# rapidshark-clip-detector-mk-1_2.net
KiCad netlist of a schematic drawn in EAGLE
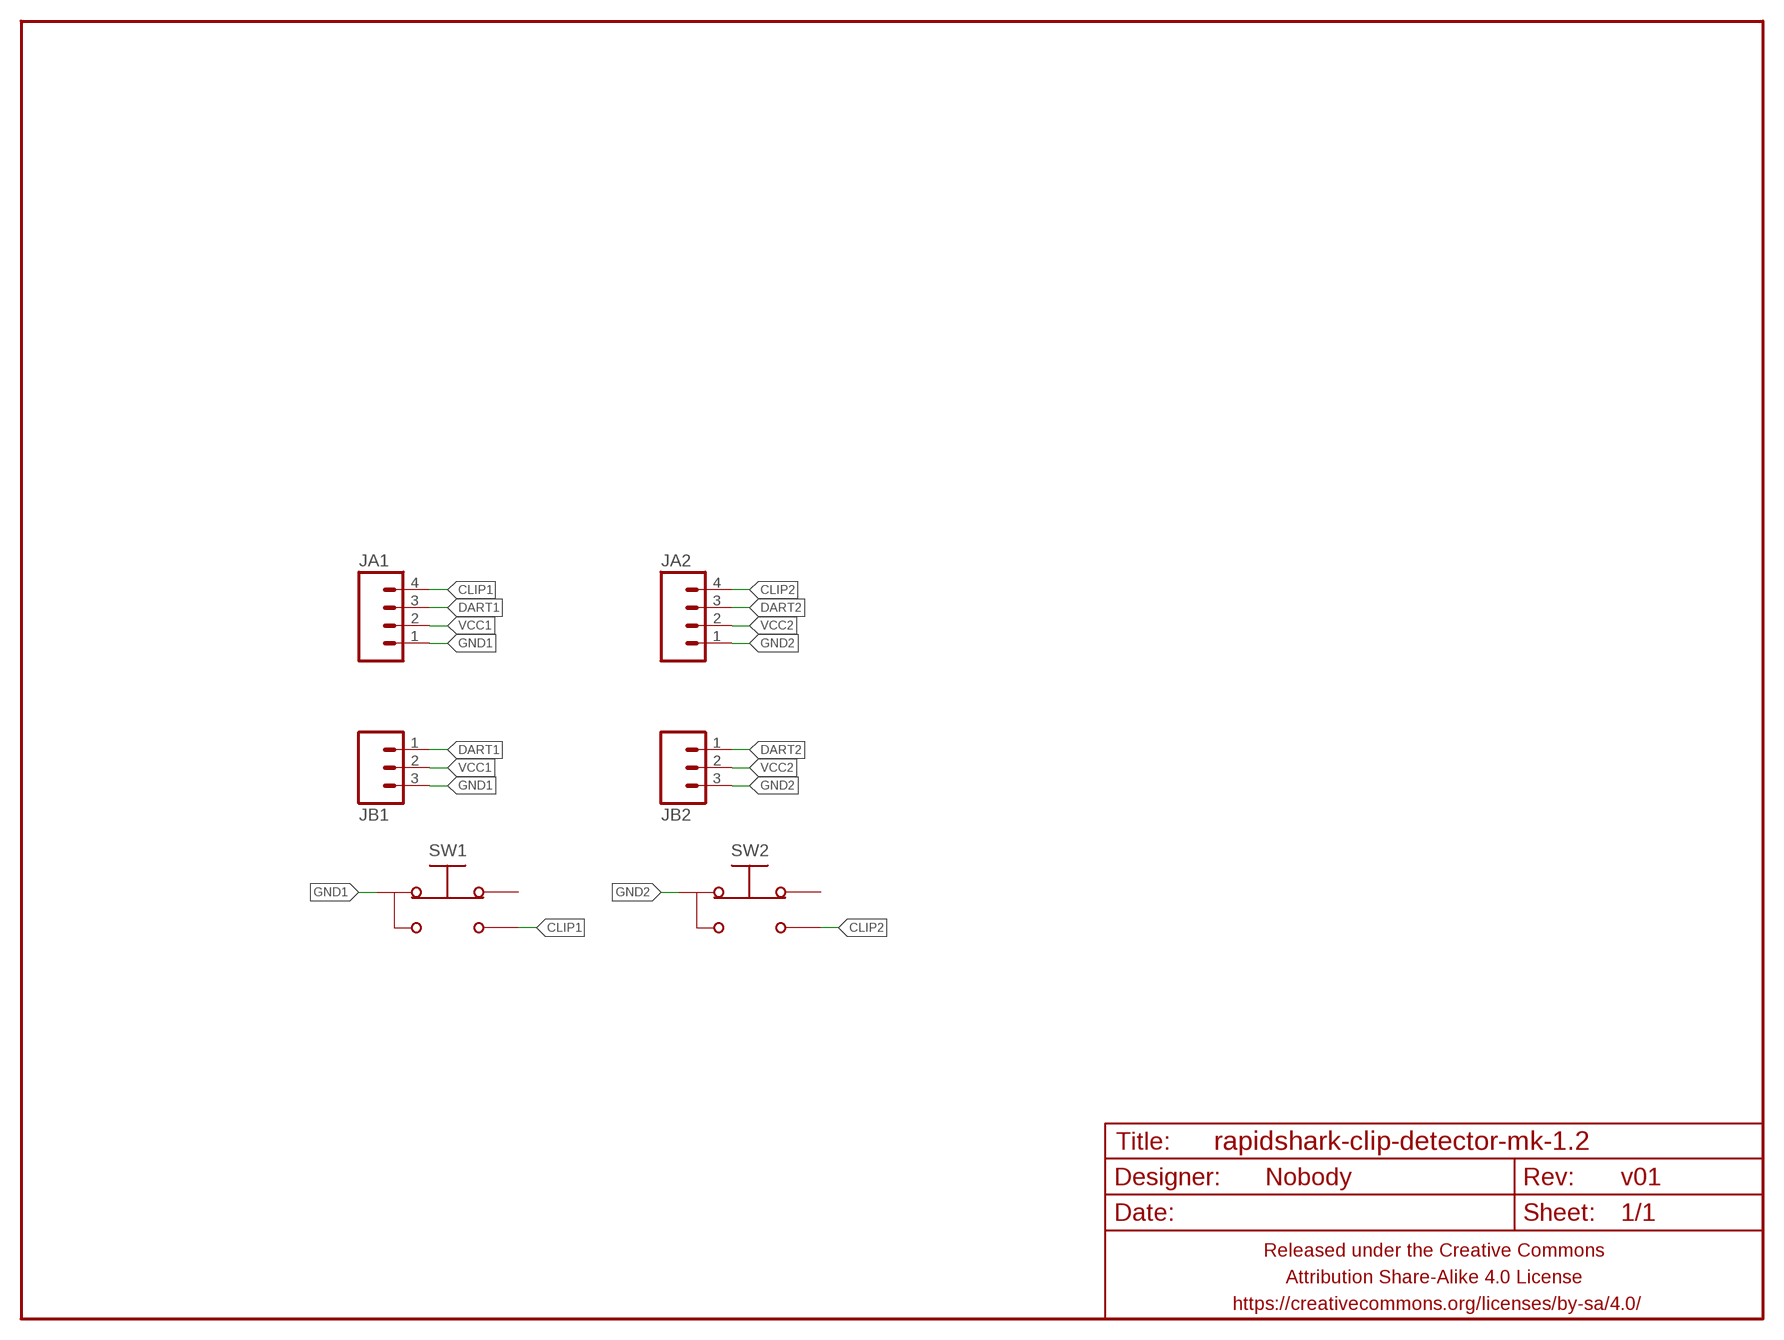
[diagram p0: schematic, sheet 1]

(export (version "E")
  (design (tool "Eeschema 10.0.6"))
  (components
    (comp (ref "FRAME1")
      (value "FRAME-LETTERNO_PACKAGE")
      (footprint "eagle-import:DUMMY")
      (fields (field (name "DESIGNER") "Nobody"))
      (libsource (lib "eagle-import") (part "FRAME-LETTERNO_PACKAGE"))
    )
    (comp (ref "JA1")
      (value "M04JST-PTH-VERT")
      (footprint "eagle-import:JST-4-PH-VERT-PTH")
      (libsource (lib "eagle-import") (part "M04JST-PTH-VERT"))
    )
    (comp (ref "JA2")
      (value "M04JST-PTH-VERT")
      (footprint "eagle-import:JST-4-PH-VERT-PTH")
      (libsource (lib "eagle-import") (part "M04JST-PTH-VERT"))
    )
    (comp (ref "JB1")
      (value "M03JST-PTH-VERT")
      (footprint "eagle-import:JST-3-PH-VERT-PTH")
      (libsource (lib "eagle-import") (part "M03JST-PTH-VERT"))
    )
    (comp (ref "JB2")
      (value "M03JST-PTH-VERT")
      (footprint "eagle-import:JST-3-PH-VERT-PTH")
      (libsource (lib "eagle-import") (part "M03JST-PTH-VERT"))
    )
    (comp (ref "SW1")
      (value "SPDT-NO-TACTPTH-RA-DETECT-3MM")
      (footprint "eagle-import:SWITCH-DETECH-SPDT-3MM")
      (libsource (lib "eagle-import") (part "SPDT-NO-TACTPTH-RA-DETECT-3MM"))
    )
    (comp (ref "SW2")
      (value "SPDT-NO-TACTPTH-RA-DETECT-3MM")
      (footprint "eagle-import:SWITCH-DETECH-SPDT-3MM")
      (libsource (lib "eagle-import") (part "SPDT-NO-TACTPTH-RA-DETECT-3MM"))
    )
  )
  (nets
    (net (code "1") (name "CLIP1") (class "Default")
      (node (ref "JA1") (pin "4") (pinfunction "4_4") (pintype "passive"))
      (node (ref "SW1") (pin "3") (pinfunction "NO_3") (pintype "bidirectional"))
    )
    (net (code "2") (name "CLIP2") (class "Default")
      (node (ref "JA2") (pin "4") (pinfunction "4_4") (pintype "passive"))
      (node (ref "SW2") (pin "3") (pinfunction "NO_3") (pintype "bidirectional"))
    )
    (net (code "3") (name "DART1") (class "Default")
      (node (ref "JA1") (pin "3") (pinfunction "3_3") (pintype "passive"))
      (node (ref "JB1") (pin "1") (pinfunction "1_1") (pintype "passive"))
    )
    (net (code "4") (name "DART2") (class "Default")
      (node (ref "JA2") (pin "3") (pinfunction "3_3") (pintype "passive"))
      (node (ref "JB2") (pin "1") (pinfunction "1_1") (pintype "passive"))
    )
    (net (code "5") (name "GND1") (class "Default")
      (node (ref "JA1") (pin "1") (pinfunction "1_1") (pintype "passive"))
      (node (ref "JB1") (pin "3") (pinfunction "3_3") (pintype "passive"))
      (node (ref "SW1") (pin "2") (pinfunction "COM_2") (pintype "bidirectional"))
    )
    (net (code "6") (name "GND2") (class "Default")
      (node (ref "JA2") (pin "1") (pinfunction "1_1") (pintype "passive"))
      (node (ref "JB2") (pin "3") (pinfunction "3_3") (pintype "passive"))
      (node (ref "SW2") (pin "2") (pinfunction "COM_2") (pintype "bidirectional"))
    )
    (net (code "7") (name "VCC1") (class "Default")
      (node (ref "JA1") (pin "2") (pinfunction "2_2") (pintype "passive"))
      (node (ref "JB1") (pin "2") (pinfunction "2_2") (pintype "passive"))
    )
    (net (code "8") (name "VCC2") (class "Default")
      (node (ref "JA2") (pin "2") (pinfunction "2_2") (pintype "passive"))
      (node (ref "JB2") (pin "2") (pinfunction "2_2") (pintype "passive"))
    )
    (net (code "9") (name "unconnected-(SW1-NC-Pad1)") (class "Default")
      (node (ref "SW1") (pin "1") (pinfunction "NC_1") (pintype "bidirectional"))
    )
    (net (code "10") (name "unconnected-(SW2-NC-Pad1)") (class "Default")
      (node (ref "SW2") (pin "1") (pinfunction "NC_1") (pintype "bidirectional"))
    )
  )
)
